# IMU.net
KiCad netlist of a schematic drawn in Altium Designer
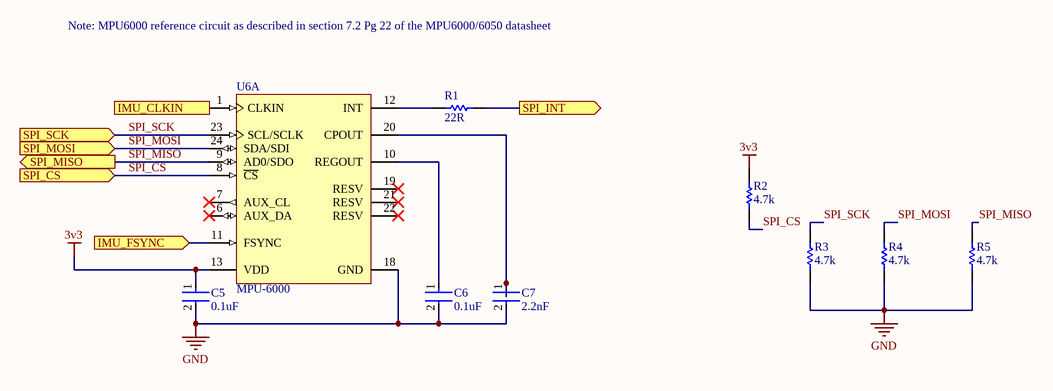
[diagram p0: IMU.SchDoc]

(export (version "E")
  (design (tool "Eeschema 10.0.6"))
  (components
    (comp (ref "C5")
      (value "0.1uF")
      (footprint "FP-CC0603-DA-IPC_C")
      (description "CAP CER 0.1UF 16V X7R 0603")
      (fields
        (field (name "OCTOPART") "https://octopart.com/cc0603krx7r7bb104-yageo-192941")
        (field (name "TOLERANCE") "0.1")
      )
      (libsource (lib "LeafLabs_Commercial") (part "CAP-0603-0.1uF"))
    )
    (comp (ref "C6")
      (value "0.1uF")
      (footprint "FP-CC0603-DA-IPC_C")
      (description "CAP CER 0.1UF 16V X7R 0603")
      (fields
        (field (name "OCTOPART") "https://octopart.com/cc0603krx7r7bb104-yageo-192941")
        (field (name "TOLERANCE") "0.1")
      )
      (libsource (lib "LeafLabs_Commercial") (part "CAP-0603-0.1uF"))
    )
    (comp (ref "C7")
      (value "2.2nF")
      (footprint "FP-CC0603-DA-IPC_C")
      (description "CAP CER 2.2nF 50V X7R 0603")
      (fields (field (name "TOLERANCE") "0.1"))
      (libsource (lib "Capacitors") (part "CAP-0603-2.2nF"))
    )
    (comp (ref "R1")
      (value "22R")
      (footprint "RESC1609X50X30LL10T20")
      (description "Resistor 0603 22 Ohm")
      (libsource (lib "Resistors") (part "RES-0603-22R"))
    )
    (comp (ref "R2")
      (value "4.7k")
      (footprint "RESC1609X50X30LL10T20")
      (description "Resistor 0603 4.7k Ohm")
      (libsource (lib "LeafLabs_Commercial") (part "RES-0603-4.7k"))
    )
    (comp (ref "R3")
      (value "4.7k")
      (footprint "RESC1609X50X30LL10T20")
      (description "Resistor 0603 4.7k Ohm")
      (libsource (lib "LeafLabs_Commercial") (part "RES-0603-4.7k"))
    )
    (comp (ref "R4")
      (value "4.7k")
      (footprint "RESC1609X50X30LL10T20")
      (description "Resistor 0603 4.7k Ohm")
      (libsource (lib "LeafLabs_Commercial") (part "RES-0603-4.7k"))
    )
    (comp (ref "R5")
      (value "4.7k")
      (footprint "RESC1609X50X30LL10T20")
      (description "Resistor 0603 4.7k Ohm")
      (libsource (lib "LeafLabs_Commercial") (part "RES-0603-4.7k"))
    )
    (comp (ref "U6")
      (value "MPU-6000")
      (footprint "QFN-24_NoPad")
      (fields (field (name "MANUFACTURER") "InvenSense"))
      (libsource (lib "Sensors") (part "MPU-6000"))
    )
  )
  (nets
    (net (code "1") (name "/IMU_CLKIN") (class "Default")
      (node (ref "U6") (pin "1") (pinfunction "CLKIN_1") (pintype "input"))
    )
    (net (code "2") (name "/IMU_FSYNC") (class "Default")
      (node (ref "U6") (pin "11") (pinfunction "FSYNC_11") (pintype "input"))
    )
    (net (code "3") (name "/SPI_CS") (class "Default")
      (node (ref "R2") (pin "1") (pinfunction "1_1") (pintype "passive"))
      (node (ref "U6") (pin "8") (pinfunction "~{CS}_8") (pintype "input"))
    )
    (net (code "4") (name "/SPI_INT") (class "Default")
      (node (ref "R1") (pin "2") (pinfunction "2_2") (pintype "passive"))
    )
    (net (code "5") (name "/SPI_MISO") (class "Default")
      (node (ref "R5") (pin "2") (pinfunction "2_2") (pintype "passive"))
      (node (ref "U6") (pin "9") (pinfunction "AD0/SDO_9") (pintype "bidirectional"))
    )
    (net (code "6") (name "/SPI_MOSI") (class "Default")
      (node (ref "R4") (pin "2") (pinfunction "2_2") (pintype "passive"))
      (node (ref "U6") (pin "24") (pinfunction "SDA/SDI_24") (pintype "bidirectional"))
    )
    (net (code "7") (name "/SPI_SCK") (class "Default")
      (node (ref "R3") (pin "2") (pinfunction "2_2") (pintype "passive"))
      (node (ref "U6") (pin "23") (pinfunction "SCL/SCLK_23") (pintype "input"))
    )
    (net (code "8") (name "3v3") (class "Default")
      (node (ref "C5") (pin "1") (pinfunction "1_1") (pintype "passive"))
      (node (ref "R2") (pin "2") (pinfunction "2_2") (pintype "passive"))
      (node (ref "U6") (pin "13") (pinfunction "VDD_13") (pintype "power_in"))
    )
    (net (code "9") (name "GND") (class "Default")
      (node (ref "C5") (pin "2") (pinfunction "2_2") (pintype "passive"))
      (node (ref "C6") (pin "2") (pinfunction "2_2") (pintype "passive"))
      (node (ref "C7") (pin "2") (pinfunction "2_2") (pintype "passive"))
      (node (ref "R3") (pin "1") (pinfunction "1_1") (pintype "passive"))
      (node (ref "R4") (pin "1") (pinfunction "1_1") (pintype "passive"))
      (node (ref "R5") (pin "1") (pinfunction "1_1") (pintype "passive"))
      (node (ref "U6") (pin "18") (pinfunction "GND_18") (pintype "power_in"))
    )
    (net (code "10") (name "Net-(U6A-CPOUT)") (class "Default")
      (node (ref "C7") (pin "1") (pinfunction "1_1") (pintype "passive"))
      (node (ref "U6") (pin "20") (pinfunction "CPOUT_20") (pintype "passive"))
    )
    (net (code "11") (name "Net-(U6A-INT)") (class "Default")
      (node (ref "R1") (pin "1") (pinfunction "1_1") (pintype "passive"))
      (node (ref "U6") (pin "12") (pinfunction "INT_12") (pintype "open_collector"))
    )
    (net (code "12") (name "Net-(U6A-REGOUT)") (class "Default")
      (node (ref "C6") (pin "1") (pinfunction "1_1") (pintype "passive"))
      (node (ref "U6") (pin "10") (pinfunction "REGOUT_10") (pintype "passive"))
    )
    (net (code "13") (name "unconnected-(U6A-AUX_CL-Pad7)") (class "Default")
      (node (ref "U6") (pin "7") (pinfunction "AUX_CL_7") (pintype "output+no_connect"))
    )
    (net (code "14") (name "unconnected-(U6A-AUX_DA-Pad6)") (class "Default")
      (node (ref "U6") (pin "6") (pinfunction "AUX_DA_6") (pintype "bidirectional+no_connect"))
    )
    (net (code "15") (name "unconnected-(U6A-RESV-Pad19)") (class "Default")
      (node (ref "U6") (pin "19") (pinfunction "RESV_19") (pintype "passive+no_connect"))
    )
    (net (code "16") (name "unconnected-(U6A-RESV-Pad21)") (class "Default")
      (node (ref "U6") (pin "21") (pinfunction "RESV_21") (pintype "passive+no_connect"))
    )
    (net (code "17") (name "unconnected-(U6A-RESV-Pad22)") (class "Default")
      (node (ref "U6") (pin "22") (pinfunction "RESV_22") (pintype "passive+no_connect"))
    )
  )
)
